# untitled.net
KiCad netlist of a schematic drawn in EAGLE
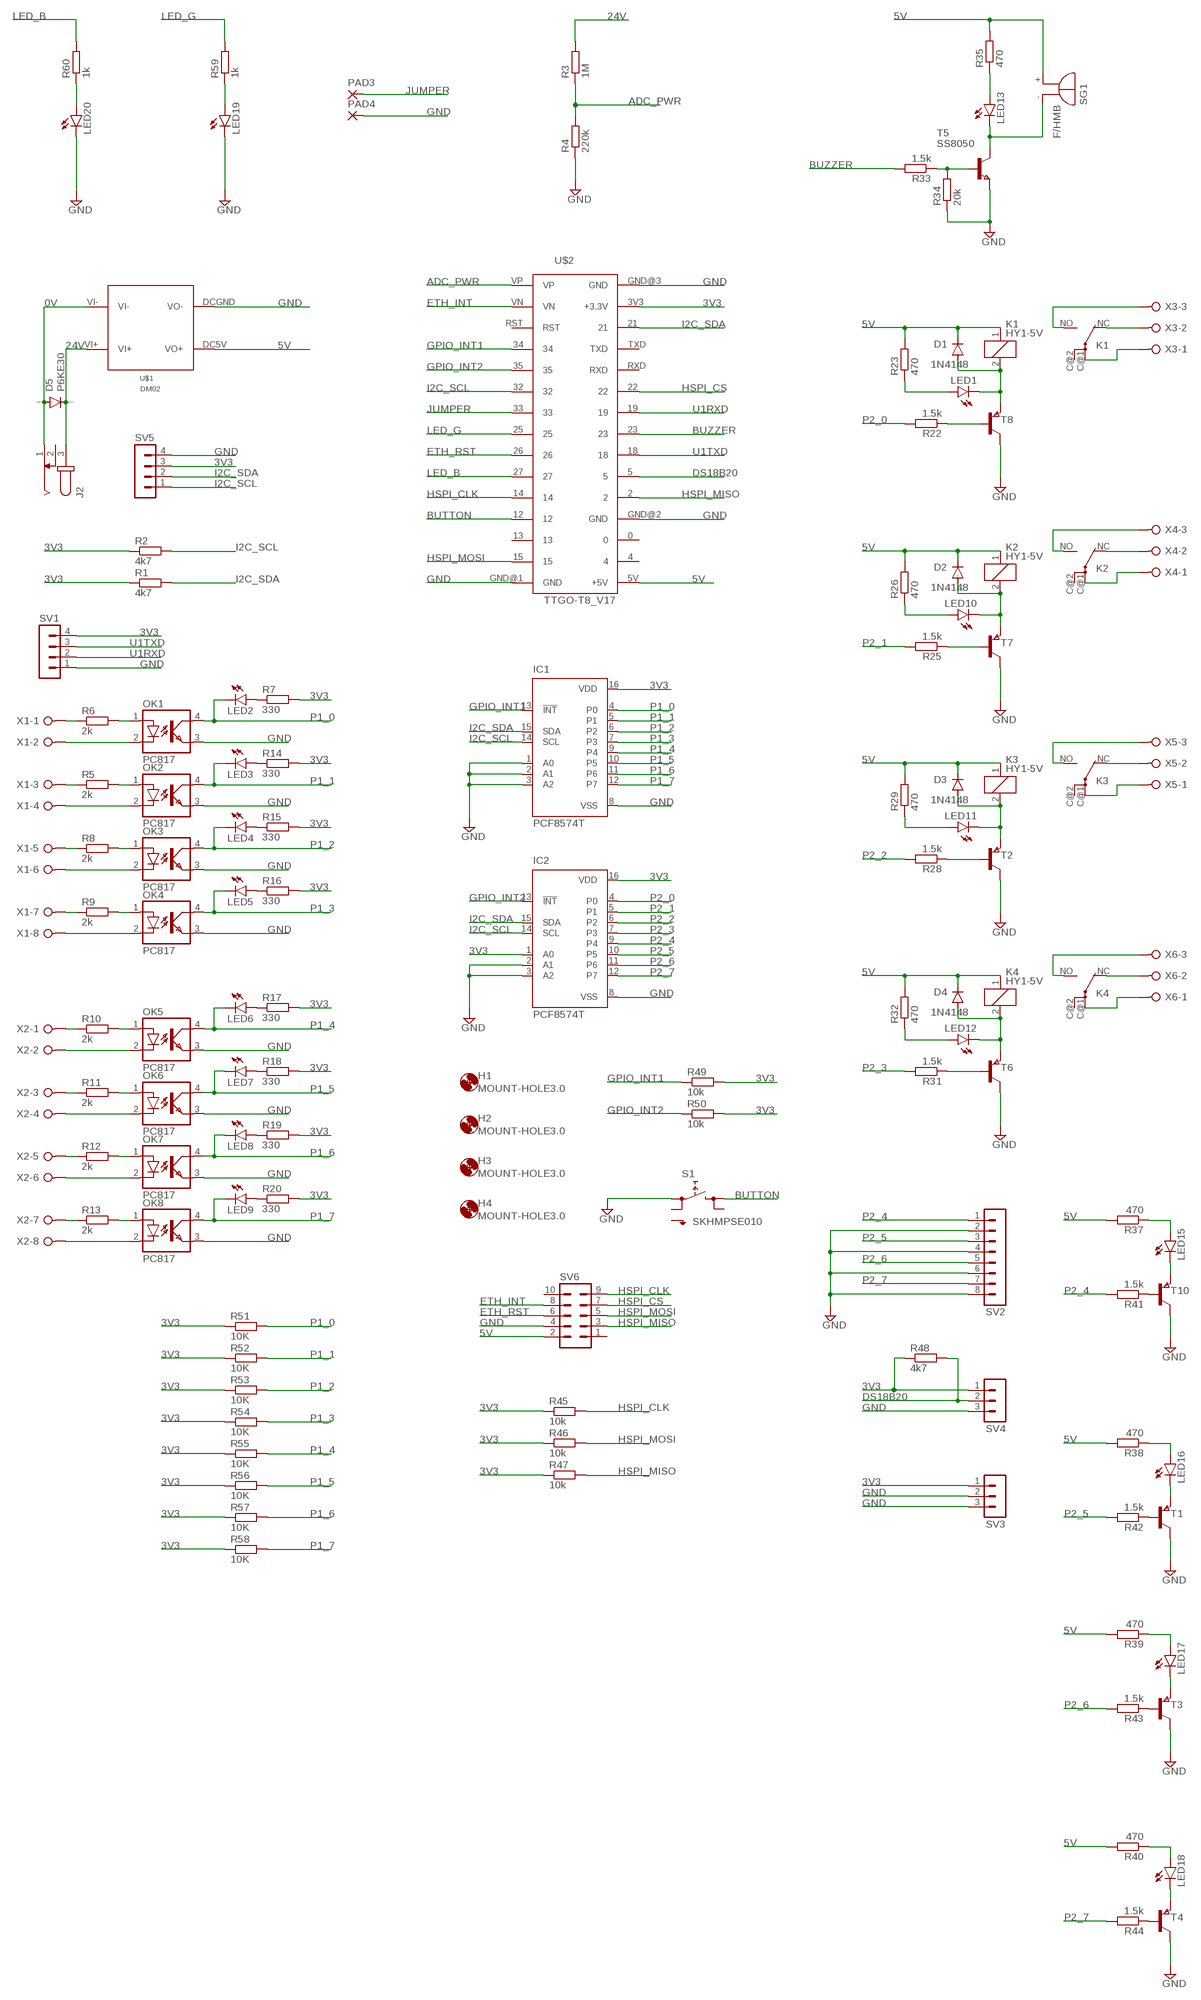
[diagram p0: schematic, sheet 1]

(export (version "E")
  (design (tool "Eeschema 10.0.6"))
  (components
    (comp (ref "D1")
      (value "1N4148")
      (footprint "eagle-import:SOD123")
      (libsource (lib "eagle-import") (part "DIODE-SOD123"))
    )
    (comp (ref "D2")
      (value "1N4148")
      (footprint "eagle-import:SOD123")
      (libsource (lib "eagle-import") (part "DIODE-SOD123"))
    )
    (comp (ref "D3")
      (value "1N4148")
      (footprint "eagle-import:SOD123")
      (libsource (lib "eagle-import") (part "DIODE-SOD123"))
    )
    (comp (ref "D4")
      (value "1N4148")
      (footprint "eagle-import:SOD123")
      (libsource (lib "eagle-import") (part "DIODE-SOD123"))
    )
    (comp (ref "D5")
      (value "P6KE30")
      (footprint "eagle-import:D-10")
      (libsource (lib "eagle-import") (part "diode@1_DIODE-D-10"))
    )
    (comp (ref "H1")
      (value "MOUNT-HOLE3.0")
      (footprint "eagle-import:3,0")
      (libsource (lib "eagle-import") (part "MOUNT-HOLE3.0"))
    )
    (comp (ref "H2")
      (value "MOUNT-HOLE3.0")
      (footprint "eagle-import:3,0")
      (libsource (lib "eagle-import") (part "MOUNT-HOLE3.0"))
    )
    (comp (ref "H3")
      (value "MOUNT-HOLE3.0")
      (footprint "eagle-import:3,0")
      (libsource (lib "eagle-import") (part "MOUNT-HOLE3.0"))
    )
    (comp (ref "H4")
      (value "MOUNT-HOLE3.0")
      (footprint "eagle-import:3,0")
      (libsource (lib "eagle-import") (part "MOUNT-HOLE3.0"))
    )
    (comp (ref "IC1")
      (value "PCF8574T")
      (footprint "eagle-import:SO16W")
      (fields (field (name "MPN") "PCF8574T/3,512"))
      (libsource (lib "eagle-import") (part "PCF8574T"))
    )
    (comp (ref "IC2")
      (value "PCF8574T")
      (footprint "eagle-import:SO16W")
      (fields (field (name "MPN") "PCF8574T/3,512"))
      (libsource (lib "eagle-import") (part "PCF8574T"))
    )
    (comp (ref "J2")
      (value "JACK-PLUG0")
      (footprint "eagle-import:SPC4077")
      (libsource (lib "eagle-import") (part "JACK-PLUG0"))
    )
    (comp (ref "K1")
      (value "HY1-5V")
      (footprint "eagle-import:HY")
      (fields (field (name "MF") "AROMAT/ MATSUSHITA"))
      (libsource (lib "eagle-import") (part "HY1-5V"))
    )
    (comp (ref "K2")
      (value "HY1-5V")
      (footprint "eagle-import:HY")
      (fields (field (name "MF") "AROMAT/ MATSUSHITA"))
      (libsource (lib "eagle-import") (part "HY1-5V"))
    )
    (comp (ref "K3")
      (value "HY1-5V")
      (footprint "eagle-import:HY")
      (fields (field (name "MF") "AROMAT/ MATSUSHITA"))
      (libsource (lib "eagle-import") (part "HY1-5V"))
    )
    (comp (ref "K4")
      (value "HY1-5V")
      (footprint "eagle-import:HY")
      (fields (field (name "MF") "AROMAT/ MATSUSHITA"))
      (libsource (lib "eagle-import") (part "HY1-5V"))
    )
    (comp (ref "LED1")
      (value "LEDCHIPLED_0805")
      (footprint "eagle-import:CHIPLED_0805")
      (libsource (lib "eagle-import") (part "LEDCHIPLED_0805"))
    )
    (comp (ref "LED2")
      (value "LEDCHIPLED_0805")
      (footprint "eagle-import:CHIPLED_0805")
      (libsource (lib "eagle-import") (part "LEDCHIPLED_0805"))
    )
    (comp (ref "LED3")
      (value "LEDCHIPLED_0805")
      (footprint "eagle-import:CHIPLED_0805")
      (libsource (lib "eagle-import") (part "LEDCHIPLED_0805"))
    )
    (comp (ref "LED4")
      (value "LEDCHIPLED_0805")
      (footprint "eagle-import:CHIPLED_0805")
      (libsource (lib "eagle-import") (part "LEDCHIPLED_0805"))
    )
    (comp (ref "LED5")
      (value "LEDCHIPLED_0805")
      (footprint "eagle-import:CHIPLED_0805")
      (libsource (lib "eagle-import") (part "LEDCHIPLED_0805"))
    )
    (comp (ref "LED6")
      (value "LEDCHIPLED_0805")
      (footprint "eagle-import:CHIPLED_0805")
      (libsource (lib "eagle-import") (part "LEDCHIPLED_0805"))
    )
    (comp (ref "LED7")
      (value "LEDCHIPLED_0805")
      (footprint "eagle-import:CHIPLED_0805")
      (libsource (lib "eagle-import") (part "LEDCHIPLED_0805"))
    )
    (comp (ref "LED8")
      (value "LEDCHIPLED_0805")
      (footprint "eagle-import:CHIPLED_0805")
      (libsource (lib "eagle-import") (part "LEDCHIPLED_0805"))
    )
    (comp (ref "LED9")
      (value "LEDCHIPLED_0805")
      (footprint "eagle-import:CHIPLED_0805")
      (libsource (lib "eagle-import") (part "LEDCHIPLED_0805"))
    )
    (comp (ref "LED10")
      (value "LEDCHIPLED_0805")
      (footprint "eagle-import:CHIPLED_0805")
      (libsource (lib "eagle-import") (part "LEDCHIPLED_0805"))
    )
    (comp (ref "LED11")
      (value "LEDCHIPLED_0805")
      (footprint "eagle-import:CHIPLED_0805")
      (libsource (lib "eagle-import") (part "LEDCHIPLED_0805"))
    )
    (comp (ref "LED12")
      (value "LEDCHIPLED_0805")
      (footprint "eagle-import:CHIPLED_0805")
      (libsource (lib "eagle-import") (part "LEDCHIPLED_0805"))
    )
    (comp (ref "LED13")
      (value "LEDCHIPLED_0805")
      (footprint "eagle-import:CHIPLED_0805")
      (libsource (lib "eagle-import") (part "LEDCHIPLED_0805"))
    )
    (comp (ref "LED15")
      (value "LEDCHIPLED_0805")
      (footprint "eagle-import:CHIPLED_0805")
      (libsource (lib "eagle-import") (part "LEDCHIPLED_0805"))
    )
    (comp (ref "LED16")
      (value "LEDCHIPLED_0805")
      (footprint "eagle-import:CHIPLED_0805")
      (libsource (lib "eagle-import") (part "LEDCHIPLED_0805"))
    )
    (comp (ref "LED17")
      (value "LEDCHIPLED_0805")
      (footprint "eagle-import:CHIPLED_0805")
      (libsource (lib "eagle-import") (part "LEDCHIPLED_0805"))
    )
    (comp (ref "LED18")
      (value "LEDCHIPLED_0805")
      (footprint "eagle-import:CHIPLED_0805")
      (libsource (lib "eagle-import") (part "LEDCHIPLED_0805"))
    )
    (comp (ref "LED19")
      (value "LEDCHIPLED_0805")
      (footprint "eagle-import:CHIPLED_0805")
      (libsource (lib "eagle-import") (part "LEDCHIPLED_0805"))
    )
    (comp (ref "LED20")
      (value "LEDCHIPLED_0805")
      (footprint "eagle-import:CHIPLED_0805")
      (libsource (lib "eagle-import") (part "LEDCHIPLED_0805"))
    )
    (comp (ref "OK1")
      (value "PC817")
      (footprint "eagle-import:DIL04")
      (fields (field (name "MPN") "PC817X4J000F"))
      (libsource (lib "eagle-import") (part "PC817"))
    )
    (comp (ref "OK2")
      (value "PC817")
      (footprint "eagle-import:DIL04")
      (fields (field (name "MPN") "PC817X4J000F"))
      (libsource (lib "eagle-import") (part "PC817"))
    )
    (comp (ref "OK3")
      (value "PC817")
      (footprint "eagle-import:DIL04")
      (fields (field (name "MPN") "PC817X4J000F"))
      (libsource (lib "eagle-import") (part "PC817"))
    )
    (comp (ref "OK4")
      (value "PC817")
      (footprint "eagle-import:DIL04")
      (fields (field (name "MPN") "PC817X4J000F"))
      (libsource (lib "eagle-import") (part "PC817"))
    )
    (comp (ref "OK5")
      (value "PC817")
      (footprint "eagle-import:DIL04")
      (fields (field (name "MPN") "PC817X4J000F"))
      (libsource (lib "eagle-import") (part "PC817"))
    )
    (comp (ref "OK6")
      (value "PC817")
      (footprint "eagle-import:DIL04")
      (fields (field (name "MPN") "PC817X4J000F"))
      (libsource (lib "eagle-import") (part "PC817"))
    )
    (comp (ref "OK7")
      (value "PC817")
      (footprint "eagle-import:DIL04")
      (fields (field (name "MPN") "PC817X4J000F"))
      (libsource (lib "eagle-import") (part "PC817"))
    )
    (comp (ref "OK8")
      (value "PC817")
      (footprint "eagle-import:DIL04")
      (fields (field (name "MPN") "PC817X4J000F"))
      (libsource (lib "eagle-import") (part "PC817"))
    )
    (comp (ref "PAD3")
      (value "2,15/1,0")
      (footprint "eagle-import:2,15_1,0")
      (libsource (lib "eagle-import") (part "2,15/1,0"))
    )
    (comp (ref "PAD4")
      (value "2,15/1,0")
      (footprint "eagle-import:2,15_1,0")
      (libsource (lib "eagle-import") (part "2,15/1,0"))
    )
    (comp (ref "R1")
      (value "4k7")
      (footprint "eagle-import:R0603")
      (libsource (lib "eagle-import") (part "R-EU_R0603"))
    )
    (comp (ref "R2")
      (value "4k7")
      (footprint "eagle-import:R0603")
      (libsource (lib "eagle-import") (part "R-EU_R0603"))
    )
    (comp (ref "R3")
      (value "1M")
      (footprint "eagle-import:R0603")
      (libsource (lib "eagle-import") (part "R-EU_R0603"))
    )
    (comp (ref "R4")
      (value "220k")
      (footprint "eagle-import:R0603")
      (libsource (lib "eagle-import") (part "R-EU_R0603"))
    )
    (comp (ref "R5")
      (value "2k")
      (footprint "eagle-import:R0603")
      (libsource (lib "eagle-import") (part "R-EU_R0603"))
    )
    (comp (ref "R6")
      (value "2k")
      (footprint "eagle-import:R0603")
      (libsource (lib "eagle-import") (part "R-EU_R0603"))
    )
    (comp (ref "R7")
      (value "330")
      (footprint "eagle-import:R0603")
      (libsource (lib "eagle-import") (part "R-EU_R0603"))
    )
    (comp (ref "R8")
      (value "2k")
      (footprint "eagle-import:R0603")
      (libsource (lib "eagle-import") (part "R-EU_R0603"))
    )
    (comp (ref "R9")
      (value "2k")
      (footprint "eagle-import:R0603")
      (libsource (lib "eagle-import") (part "R-EU_R0603"))
    )
    (comp (ref "R10")
      (value "2k")
      (footprint "eagle-import:R0603")
      (libsource (lib "eagle-import") (part "R-EU_R0603"))
    )
    (comp (ref "R11")
      (value "2k")
      (footprint "eagle-import:R0603")
      (libsource (lib "eagle-import") (part "R-EU_R0603"))
    )
    (comp (ref "R12")
      (value "2k")
      (footprint "eagle-import:R0603")
      (libsource (lib "eagle-import") (part "R-EU_R0603"))
    )
    (comp (ref "R13")
      (value "2k")
      (footprint "eagle-import:R0603")
      (libsource (lib "eagle-import") (part "R-EU_R0603"))
    )
    (comp (ref "R14")
      (value "330")
      (footprint "eagle-import:R0603")
      (libsource (lib "eagle-import") (part "R-EU_R0603"))
    )
    (comp (ref "R15")
      (value "330")
      (footprint "eagle-import:R0603")
      (libsource (lib "eagle-import") (part "R-EU_R0603"))
    )
    (comp (ref "R16")
      (value "330")
      (footprint "eagle-import:R0603")
      (libsource (lib "eagle-import") (part "R-EU_R0603"))
    )
    (comp (ref "R17")
      (value "330")
      (footprint "eagle-import:R0603")
      (libsource (lib "eagle-import") (part "R-EU_R0603"))
    )
    (comp (ref "R18")
      (value "330")
      (footprint "eagle-import:R0603")
      (libsource (lib "eagle-import") (part "R-EU_R0603"))
    )
    (comp (ref "R19")
      (value "330")
      (footprint "eagle-import:R0603")
      (libsource (lib "eagle-import") (part "R-EU_R0603"))
    )
    (comp (ref "R20")
      (value "330")
      (footprint "eagle-import:R0603")
      (libsource (lib "eagle-import") (part "R-EU_R0603"))
    )
    (comp (ref "R22")
      (value "1.5k")
      (footprint "eagle-import:R0603")
      (libsource (lib "eagle-import") (part "R-EU_R0603"))
    )
    (comp (ref "R23")
      (value "470")
      (footprint "eagle-import:R0603")
      (libsource (lib "eagle-import") (part "R-EU_R0603"))
    )
    (comp (ref "R25")
      (value "1.5k")
      (footprint "eagle-import:R0603")
      (libsource (lib "eagle-import") (part "R-EU_R0603"))
    )
    (comp (ref "R26")
      (value "470")
      (footprint "eagle-import:R0603")
      (libsource (lib "eagle-import") (part "R-EU_R0603"))
    )
    (comp (ref "R28")
      (value "1.5k")
      (footprint "eagle-import:R0603")
      (libsource (lib "eagle-import") (part "R-EU_R0603"))
    )
    (comp (ref "R29")
      (value "470")
      (footprint "eagle-import:R0603")
      (libsource (lib "eagle-import") (part "R-EU_R0603"))
    )
    (comp (ref "R31")
      (value "1.5k")
      (footprint "eagle-import:R0603")
      (libsource (lib "eagle-import") (part "R-EU_R0603"))
    )
    (comp (ref "R32")
      (value "470")
      (footprint "eagle-import:R0603")
      (libsource (lib "eagle-import") (part "R-EU_R0603"))
    )
    (comp (ref "R33")
      (value "1.5k")
      (footprint "eagle-import:R0603")
      (libsource (lib "eagle-import") (part "R-EU_R0603"))
    )
    (comp (ref "R34")
      (value "20k")
      (footprint "eagle-import:R0603")
      (libsource (lib "eagle-import") (part "R-EU_R0603"))
    )
    (comp (ref "R35")
      (value "470")
      (footprint "eagle-import:R0603")
      (libsource (lib "eagle-import") (part "R-EU_R0603"))
    )
    (comp (ref "R37")
      (value "470")
      (footprint "eagle-import:R0603")
      (libsource (lib "eagle-import") (part "R-EU_R0603"))
    )
    (comp (ref "R38")
      (value "470")
      (footprint "eagle-import:R0603")
      (libsource (lib "eagle-import") (part "R-EU_R0603"))
    )
    (comp (ref "R39")
      (value "470")
      (footprint "eagle-import:R0603")
      (libsource (lib "eagle-import") (part "R-EU_R0603"))
    )
    (comp (ref "R40")
      (value "470")
      (footprint "eagle-import:R0603")
      (libsource (lib "eagle-import") (part "R-EU_R0603"))
    )
    (comp (ref "R41")
      (value "1.5k")
      (footprint "eagle-import:R0603")
      (libsource (lib "eagle-import") (part "R-EU_R0603"))
    )
    (comp (ref "R42")
      (value "1.5k")
      (footprint "eagle-import:R0603")
      (libsource (lib "eagle-import") (part "R-EU_R0603"))
    )
    (comp (ref "R43")
      (value "1.5k")
      (footprint "eagle-import:R0603")
      (libsource (lib "eagle-import") (part "R-EU_R0603"))
    )
    (comp (ref "R44")
      (value "1.5k")
      (footprint "eagle-import:R0603")
      (libsource (lib "eagle-import") (part "R-EU_R0603"))
    )
    (comp (ref "R45")
      (value "10k")
      (footprint "eagle-import:R0603")
      (libsource (lib "eagle-import") (part "R-EU_R0603"))
    )
    (comp (ref "R46")
      (value "10k")
      (footprint "eagle-import:R0603")
      (libsource (lib "eagle-import") (part "R-EU_R0603"))
    )
    (comp (ref "R47")
      (value "10k")
      (footprint "eagle-import:R0603")
      (libsource (lib "eagle-import") (part "R-EU_R0603"))
    )
    (comp (ref "R48")
      (value "4k7")
      (footprint "eagle-import:R0603")
      (libsource (lib "eagle-import") (part "R-EU_R0603"))
    )
    (comp (ref "R49")
      (value "10k")
      (footprint "eagle-import:R0603")
      (libsource (lib "eagle-import") (part "R-EU_R0603"))
    )
    (comp (ref "R50")
      (value "10k")
      (footprint "eagle-import:R0603")
      (libsource (lib "eagle-import") (part "R-EU_R0603"))
    )
    (comp (ref "R51")
      (value "10K")
      (footprint "eagle-import:R0603")
      (libsource (lib "eagle-import") (part "R-EU_R0603"))
    )
    (comp (ref "R52")
      (value "10K")
      (footprint "eagle-import:R0603")
      (libsource (lib "eagle-import") (part "R-EU_R0603"))
    )
    (comp (ref "R53")
      (value "10K")
      (footprint "eagle-import:R0603")
      (libsource (lib "eagle-import") (part "R-EU_R0603"))
    )
    (comp (ref "R54")
      (value "10K")
      (footprint "eagle-import:R0603")
      (libsource (lib "eagle-import") (part "R-EU_R0603"))
    )
    (comp (ref "R55")
      (value "10K")
      (footprint "eagle-import:R0603")
      (libsource (lib "eagle-import") (part "R-EU_R0603"))
    )
    (comp (ref "R56")
      (value "10K")
      (footprint "eagle-import:R0603")
      (libsource (lib "eagle-import") (part "R-EU_R0603"))
    )
    (comp (ref "R57")
      (value "10K")
      (footprint "eagle-import:R0603")
      (libsource (lib "eagle-import") (part "R-EU_R0603"))
    )
    (comp (ref "R58")
      (value "10K")
      (footprint "eagle-import:R0603")
      (libsource (lib "eagle-import") (part "R-EU_R0603"))
    )
    (comp (ref "R59")
      (value "1k")
      (footprint "eagle-import:R0603")
      (libsource (lib "eagle-import") (part "R-EU_R0603"))
    )
    (comp (ref "R60")
      (value "1k")
      (footprint "eagle-import:R0603")
      (libsource (lib "eagle-import") (part "R-EU_R0603"))
    )
    (comp (ref "S1")
      (value "SKHMPSE010")
      (footprint "eagle-import:SKHMPXE010")
      (libsource (lib "eagle-import") (part "SKHMPE010S"))
    )
    (comp (ref "SG1")
      (value "F/HMB")
      (footprint "eagle-import:F_HMB")
      (libsource (lib "eagle-import") (part "F/HMB"))
    )
    (comp (ref "SV1")
      (value "MA04-1")
      (footprint "eagle-import:MA04-1")
      (libsource (lib "eagle-import") (part "MA04-1"))
    )
    (comp (ref "SV2")
      (value "MA08-1")
      (footprint "eagle-import:MA08-1")
      (libsource (lib "eagle-import") (part "MA08-1"))
    )
    (comp (ref "SV3")
      (value "MA03-1")
      (footprint "eagle-import:MA03-1")
      (libsource (lib "eagle-import") (part "MA03-1"))
    )
    (comp (ref "SV4")
      (value "MA03-1")
      (footprint "eagle-import:MA03-1")
      (libsource (lib "eagle-import") (part "MA03-1"))
    )
    (comp (ref "SV5")
      (value "MA04-1")
      (footprint "eagle-import:MA04-1")
      (libsource (lib "eagle-import") (part "MA04-1"))
    )
    (comp (ref "SV6")
      (value "MA05-2")
      (footprint "eagle-import:MA05-2")
      (libsource (lib "eagle-import") (part "MA05-2"))
    )
    (comp (ref "T1")
      (value "PNPSOT23")
      (footprint "eagle-import:SOT-23")
      (fields (field (name "MPN") "DSS20200L-7"))
      (libsource (lib "eagle-import") (part "PNPSOT23"))
    )
    (comp (ref "T2")
      (value "PNPSOT23")
      (footprint "eagle-import:SOT-23")
      (fields (field (name "MPN") "DSS20200L-7"))
      (libsource (lib "eagle-import") (part "PNPSOT23"))
    )
    (comp (ref "T3")
      (value "PNPSOT23")
      (footprint "eagle-import:SOT-23")
      (fields (field (name "MPN") "DSS20200L-7"))
      (libsource (lib "eagle-import") (part "PNPSOT23"))
    )
    (comp (ref "T4")
      (value "PNPSOT23")
      (footprint "eagle-import:SOT-23")
      (fields (field (name "MPN") "DSS20200L-7"))
      (libsource (lib "eagle-import") (part "PNPSOT23"))
    )
    (comp (ref "T5")
      (value "SS8050")
      (footprint "eagle-import:SOT-23")
      (fields (field (name "MPN") "DSS20201L-7"))
      (libsource (lib "eagle-import") (part "NPNSOT23"))
    )
    (comp (ref "T6")
      (value "PNPSOT23")
      (footprint "eagle-import:SOT-23")
      (fields (field (name "MPN") "DSS20200L-7"))
      (libsource (lib "eagle-import") (part "PNPSOT23"))
    )
    (comp (ref "T7")
      (value "PNPSOT23")
      (footprint "eagle-import:SOT-23")
      (fields (field (name "MPN") "DSS20200L-7"))
      (libsource (lib "eagle-import") (part "PNPSOT23"))
    )
    (comp (ref "T8")
      (value "PNPSOT23")
      (footprint "eagle-import:SOT-23")
      (fields (field (name "MPN") "DSS20200L-7"))
      (libsource (lib "eagle-import") (part "PNPSOT23"))
    )
    (comp (ref "T10")
      (value "PNPSOT23")
      (footprint "eagle-import:SOT-23")
      (fields (field (name "MPN") "DSS20200L-7"))
      (libsource (lib "eagle-import") (part "PNPSOT23"))
    )
    (comp (ref "U$1")
      (value "DM02")
      (footprint "eagle-import:DM02")
      (libsource (lib "eagle-import") (part "DM02"))
    )
    (comp (ref "U$2")
      (value "TTGO-T8_V17")
      (footprint "eagle-import:TTGO-T8_V17")
      (libsource (lib "eagle-import") (part "TTGO-T8_V17"))
    )
    (comp (ref "X1")
      (value "W237-08P")
      (footprint "eagle-import:W237-8P")
      (libsource (lib "eagle-import") (part "W237-08P"))
    )
    (comp (ref "X2")
      (value "W237-08P")
      (footprint "eagle-import:W237-8P")
      (libsource (lib "eagle-import") (part "W237-08P"))
    )
    (comp (ref "X3")
      (value "W237-03P")
      (footprint "eagle-import:W237-133")
      (libsource (lib "eagle-import") (part "W237-03P"))
    )
    (comp (ref "X4")
      (value "W237-03P")
      (footprint "eagle-import:W237-133")
      (libsource (lib "eagle-import") (part "W237-03P"))
    )
    (comp (ref "X5")
      (value "W237-03P")
      (footprint "eagle-import:W237-133")
      (libsource (lib "eagle-import") (part "W237-03P"))
    )
    (comp (ref "X6")
      (value "W237-03P")
      (footprint "eagle-import:W237-133")
      (libsource (lib "eagle-import") (part "W237-03P"))
    )
  )
  (nets
    (net (code "1") (name "/0V") (class "Default")
      (node (ref "D5") (pin "A") (pinfunction "A_A") (pintype "passive"))
      (node (ref "J2") (pin "1") (pinfunction "1_1") (pintype "passive"))
      (node (ref "U$1") (pin "VI-") (pinfunction "VI-_VI-") (pintype "bidirectional"))
    )
    (net (code "2") (name "/3V3") (class "Default")
      (node (ref "IC1") (pin "16") (pinfunction "VDD_16") (pintype "power_in"))
      (node (ref "IC2") (pin "1") (pinfunction "A0_1") (pintype "input"))
      (node (ref "IC2") (pin "16") (pinfunction "VDD_16") (pintype "power_in"))
      (node (ref "R1") (pin "1") (pinfunction "1_1") (pintype "passive"))
      (node (ref "R14") (pin "2") (pinfunction "2_2") (pintype "passive"))
      (node (ref "R15") (pin "2") (pinfunction "2_2") (pintype "passive"))
      (node (ref "R16") (pin "2") (pinfunction "2_2") (pintype "passive"))
      (node (ref "R17") (pin "2") (pinfunction "2_2") (pintype "passive"))
      (node (ref "R18") (pin "2") (pinfunction "2_2") (pintype "passive"))
      (node (ref "R19") (pin "2") (pinfunction "2_2") (pintype "passive"))
      (node (ref "R2") (pin "1") (pinfunction "1_1") (pintype "passive"))
      (node (ref "R20") (pin "2") (pinfunction "2_2") (pintype "passive"))
      (node (ref "R45") (pin "1") (pinfunction "1_1") (pintype "passive"))
      (node (ref "R46") (pin "1") (pinfunction "1_1") (pintype "passive"))
      (node (ref "R47") (pin "1") (pinfunction "1_1") (pintype "passive"))
      (node (ref "R48") (pin "1") (pinfunction "1_1") (pintype "passive"))
      (node (ref "R49") (pin "2") (pinfunction "2_2") (pintype "passive"))
      (node (ref "R50") (pin "2") (pinfunction "2_2") (pintype "passive"))
      (node (ref "R51") (pin "1") (pinfunction "1_1") (pintype "passive"))
      (node (ref "R52") (pin "1") (pinfunction "1_1") (pintype "passive"))
      (node (ref "R53") (pin "1") (pinfunction "1_1") (pintype "passive"))
      (node (ref "R54") (pin "1") (pinfunction "1_1") (pintype "passive"))
      (node (ref "R55") (pin "1") (pinfunction "1_1") (pintype "passive"))
      (node (ref "R56") (pin "1") (pinfunction "1_1") (pintype "passive"))
      (node (ref "R57") (pin "1") (pinfunction "1_1") (pintype "passive"))
      (node (ref "R58") (pin "1") (pinfunction "1_1") (pintype "passive"))
      (node (ref "R7") (pin "2") (pinfunction "2_2") (pintype "passive"))
      (node (ref "SV1") (pin "4") (pinfunction "4_4") (pintype "passive"))
      (node (ref "SV3") (pin "1") (pinfunction "1_1") (pintype "passive"))
      (node (ref "SV4") (pin "1") (pinfunction "1_1") (pintype "passive"))
      (node (ref "SV5") (pin "3") (pinfunction "3_3") (pintype "passive"))
      (node (ref "U$2") (pin "3V3") (pinfunction "+3.3V_3V3") (pintype "bidirectional"))
    )
    (net (code "3") (name "/5V") (class "Default")
      (node (ref "D1") (pin "C") (pinfunction "C_C") (pintype "passive"))
      (node (ref "D2") (pin "C") (pinfunction "C_C") (pintype "passive"))
      (node (ref "D3") (pin "C") (pinfunction "C_C") (pintype "passive"))
      (node (ref "D4") (pin "C") (pinfunction "C_C") (pintype "passive"))
      (node (ref "K1") (pin "1") (pinfunction "1_1") (pintype "passive"))
      (node (ref "K2") (pin "1") (pinfunction "1_1") (pintype "passive"))
      (node (ref "K3") (pin "1") (pinfunction "1_1") (pintype "passive"))
      (node (ref "K4") (pin "1") (pinfunction "1_1") (pintype "passive"))
      (node (ref "R23") (pin "2") (pinfunction "2_2") (pintype "passive"))
      (node (ref "R26") (pin "2") (pinfunction "2_2") (pintype "passive"))
      (node (ref "R29") (pin "2") (pinfunction "2_2") (pintype "passive"))
      (node (ref "R32") (pin "2") (pinfunction "2_2") (pintype "passive"))
      (node (ref "R35") (pin "2") (pinfunction "2_2") (pintype "passive"))
      (node (ref "R37") (pin "2") (pinfunction "2_2") (pintype "passive"))
      (node (ref "R38") (pin "2") (pinfunction "2_2") (pintype "passive"))
      (node (ref "R39") (pin "2") (pinfunction "2_2") (pintype "passive"))
      (node (ref "R40") (pin "2") (pinfunction "2_2") (pintype "passive"))
      (node (ref "SG1") (pin "+") (pinfunction "+_+") (pintype "passive"))
      (node (ref "SV6") (pin "2") (pinfunction "2_2") (pintype "passive"))
      (node (ref "U$1") (pin "DC5V") (pinfunction "VO+_DC5V") (pintype "bidirectional"))
      (node (ref "U$2") (pin "5V") (pinfunction "+5V_5V") (pintype "bidirectional"))
    )
    (net (code "4") (name "/24V") (class "Default")
      (node (ref "D5") (pin "C") (pinfunction "C_C") (pintype "passive"))
      (node (ref "J2") (pin "3") (pinfunction "3_3") (pintype "passive"))
      (node (ref "R3") (pin "2") (pinfunction "2_2") (pintype "passive"))
      (node (ref "U$1") (pin "VI+") (pinfunction "VI+_VI+") (pintype "bidirectional"))
    )
    (net (code "5") (name "/ADC_PWR") (class "Default")
      (node (ref "R3") (pin "1") (pinfunction "1_1") (pintype "passive"))
      (node (ref "R4") (pin "2") (pinfunction "2_2") (pintype "passive"))
      (node (ref "U$2") (pin "VP") (pinfunction "VP_VP") (pintype "bidirectional"))
    )
    (net (code "6") (name "/BUTTON") (class "Default")
      (node (ref "S1") (pin "3") (pinfunction "2.1_3") (pintype "passive"))
      (node (ref "U$2") (pin "12") (pinfunction "12_12") (pintype "bidirectional"))
    )
    (net (code "7") (name "/BUZZER") (class "Default")
      (node (ref "R33") (pin "2") (pinfunction "2_2") (pintype "passive"))
      (node (ref "U$2") (pin "23") (pinfunction "23_23") (pintype "bidirectional"))
    )
    (net (code "8") (name "/DS18B20") (class "Default")
      (node (ref "R48") (pin "2") (pinfunction "2_2") (pintype "passive"))
      (node (ref "SV4") (pin "2") (pinfunction "2_2") (pintype "passive"))
      (node (ref "U$2") (pin "5") (pinfunction "5_5") (pintype "bidirectional"))
    )
    (net (code "9") (name "/ETH_INT") (class "Default")
      (node (ref "SV6") (pin "8") (pinfunction "8_8") (pintype "passive"))
      (node (ref "U$2") (pin "VN") (pinfunction "VN_VN") (pintype "bidirectional"))
    )
    (net (code "10") (name "/ETH_RST") (class "Default")
      (node (ref "SV6") (pin "6") (pinfunction "6_6") (pintype "passive"))
      (node (ref "U$2") (pin "26") (pinfunction "26_26") (pintype "bidirectional"))
    )
    (net (code "11") (name "/GPIO_INT1") (class "Default")
      (node (ref "IC1") (pin "13") (pinfunction "~{INT}_13") (pintype "output"))
      (node (ref "R49") (pin "1") (pinfunction "1_1") (pintype "passive"))
      (node (ref "U$2") (pin "34") (pinfunction "34_34") (pintype "bidirectional"))
    )
    (net (code "12") (name "/GPIO_INT2") (class "Default")
      (node (ref "IC2") (pin "13") (pinfunction "~{INT}_13") (pintype "output"))
      (node (ref "R50") (pin "1") (pinfunction "1_1") (pintype "passive"))
      (node (ref "U$2") (pin "35") (pinfunction "35_35") (pintype "bidirectional"))
    )
    (net (code "13") (name "/HSPI_CLK") (class "Default")
      (node (ref "R45") (pin "2") (pinfunction "2_2") (pintype "passive"))
      (node (ref "SV6") (pin "9") (pinfunction "9_9") (pintype "passive"))
      (node (ref "U$2") (pin "14") (pinfunction "14_14") (pintype "bidirectional"))
    )
    (net (code "14") (name "/HSPI_CS") (class "Default")
      (node (ref "SV6") (pin "7") (pinfunction "7_7") (pintype "passive"))
      (node (ref "U$2") (pin "22") (pinfunction "22_22") (pintype "bidirectional"))
    )
    (net (code "15") (name "/HSPI_MISO") (class "Default")
      (node (ref "R47") (pin "2") (pinfunction "2_2") (pintype "passive"))
      (node (ref "SV6") (pin "3") (pinfunction "3_3") (pintype "passive"))
      (node (ref "U$2") (pin "2") (pinfunction "2_2") (pintype "bidirectional"))
    )
    (net (code "16") (name "/HSPI_MOSI") (class "Default")
      (node (ref "R46") (pin "2") (pinfunction "2_2") (pintype "passive"))
      (node (ref "SV6") (pin "5") (pinfunction "5_5") (pintype "passive"))
      (node (ref "U$2") (pin "15") (pinfunction "15_15") (pintype "bidirectional"))
    )
    (net (code "17") (name "/I2C_SCL") (class "Default")
      (node (ref "IC1") (pin "14") (pinfunction "SCL_14") (pintype "input"))
      (node (ref "IC2") (pin "14") (pinfunction "SCL_14") (pintype "input"))
      (node (ref "R2") (pin "2") (pinfunction "2_2") (pintype "passive"))
      (node (ref "SV5") (pin "1") (pinfunction "1_1") (pintype "passive"))
      (node (ref "U$2") (pin "32") (pinfunction "32_32") (pintype "bidirectional"))
    )
    (net (code "18") (name "/I2C_SDA") (class "Default")
      (node (ref "IC1") (pin "15") (pinfunction "SDA_15") (pintype "bidirectional"))
      (node (ref "IC2") (pin "15") (pinfunction "SDA_15") (pintype "bidirectional"))
      (node (ref "R1") (pin "2") (pinfunction "2_2") (pintype "passive"))
      (node (ref "SV5") (pin "2") (pinfunction "2_2") (pintype "passive"))
      (node (ref "U$2") (pin "21") (pinfunction "21_21") (pintype "bidirectional"))
    )
    (net (code "19") (name "/JUMPER") (class "Default")
      (node (ref "PAD3") (pin "1") (pinfunction "P_1") (pintype "passive"))
      (node (ref "U$2") (pin "33") (pinfunction "33_33") (pintype "bidirectional"))
    )
    (net (code "20") (name "/LED_B") (class "Default")
      (node (ref "R60") (pin "2") (pinfunction "2_2") (pintype "passive"))
      (node (ref "U$2") (pin "27") (pinfunction "27_27") (pintype "bidirectional"))
    )
    (net (code "21") (name "/LED_G") (class "Default")
      (node (ref "R59") (pin "2") (pinfunction "2_2") (pintype "passive"))
      (node (ref "U$2") (pin "25") (pinfunction "25_25") (pintype "bidirectional"))
    )
    (net (code "22") (name "/P1_0") (class "Default")
      (node (ref "IC1") (pin "4") (pinfunction "P0_4") (pintype "bidirectional"))
      (node (ref "LED2") (pin "C") (pinfunction "C_C") (pintype "passive"))
      (node (ref "OK1") (pin "4") (pinfunction "COL_4") (pintype "passive"))
      (node (ref "R51") (pin "2") (pinfunction "2_2") (pintype "passive"))
    )
    (net (code "23") (name "/P1_1") (class "Default")
      (node (ref "IC1") (pin "5") (pinfunction "P1_5") (pintype "bidirectional"))
      (node (ref "LED3") (pin "C") (pinfunction "C_C") (pintype "passive"))
      (node (ref "OK2") (pin "4") (pinfunction "COL_4") (pintype "passive"))
      (node (ref "R52") (pin "2") (pinfunction "2_2") (pintype "passive"))
    )
    (net (code "24") (name "/P1_2") (class "Default")
      (node (ref "IC1") (pin "6") (pinfunction "P2_6") (pintype "bidirectional"))
      (node (ref "LED4") (pin "C") (pinfunction "C_C") (pintype "passive"))
      (node (ref "OK3") (pin "4") (pinfunction "COL_4") (pintype "passive"))
      (node (ref "R53") (pin "2") (pinfunction "2_2") (pintype "passive"))
    )
    (net (code "25") (name "/P1_3") (class "Default")
      (node (ref "IC1") (pin "7") (pinfunction "P3_7") (pintype "bidirectional"))
      (node (ref "LED5") (pin "C") (pinfunction "C_C") (pintype "passive"))
      (node (ref "OK4") (pin "4") (pinfunction "COL_4") (pintype "passive"))
      (node (ref "R54") (pin "2") (pinfunction "2_2") (pintype "passive"))
    )
    (net (code "26") (name "/P1_4") (class "Default")
      (node (ref "IC1") (pin "9") (pinfunction "P4_9") (pintype "bidirectional"))
      (node (ref "LED6") (pin "C") (pinfunction "C_C") (pintype "passive"))
      (node (ref "OK5") (pin "4") (pinfunction "COL_4") (pintype "passive"))
      (node (ref "R55") (pin "2") (pinfunction "2_2") (pintype "passive"))
    )
    (net (code "27") (name "/P1_5") (class "Default")
      (node (ref "IC1") (pin "10") (pinfunction "P5_10") (pintype "bidirectional"))
      (node (ref "LED7") (pin "C") (pinfunction "C_C") (pintype "passive"))
      (node (ref "OK6") (pin "4") (pinfunction "COL_4") (pintype "passive"))
      (node (ref "R56") (pin "2") (pinfunction "2_2") (pintype "passive"))
    )
    (net (code "28") (name "/P1_6") (class "Default")
      (node (ref "IC1") (pin "11") (pinfunction "P6_11") (pintype "bidirectional"))
      (node (ref "LED8") (pin "C") (pinfunction "C_C") (pintype "passive"))
      (node (ref "OK7") (pin "4") (pinfunction "COL_4") (pintype "passive"))
      (node (ref "R57") (pin "2") (pinfunction "2_2") (pintype "passive"))
    )
    (net (code "29") (name "/P1_7") (class "Default")
      (node (ref "IC1") (pin "12") (pinfunction "P7_12") (pintype "bidirectional"))
      (node (ref "LED9") (pin "C") (pinfunction "C_C") (pintype "passive"))
      (node (ref "OK8") (pin "4") (pinfunction "COL_4") (pintype "passive"))
      (node (ref "R58") (pin "2") (pinfunction "2_2") (pintype "passive"))
    )
    (net (code "30") (name "/P2_0") (class "Default")
      (node (ref "IC2") (pin "4") (pinfunction "P0_4") (pintype "bidirectional"))
      (node (ref "R22") (pin "2") (pinfunction "2_2") (pintype "passive"))
    )
    (net (code "31") (name "/P2_1") (class "Default")
      (node (ref "IC2") (pin "5") (pinfunction "P1_5") (pintype "bidirectional"))
      (node (ref "R25") (pin "2") (pinfunction "2_2") (pintype "passive"))
    )
    (net (code "32") (name "/P2_2") (class "Default")
      (node (ref "IC2") (pin "6") (pinfunction "P2_6") (pintype "bidirectional"))
      (node (ref "R28") (pin "2") (pinfunction "2_2") (pintype "passive"))
    )
    (net (code "33") (name "/P2_3") (class "Default")
      (node (ref "IC2") (pin "7") (pinfunction "P3_7") (pintype "bidirectional"))
      (node (ref "R31") (pin "2") (pinfunction "2_2") (pintype "passive"))
    )
    (net (code "34") (name "/P2_4") (class "Default")
      (node (ref "IC2") (pin "9") (pinfunction "P4_9") (pintype "bidirectional"))
      (node (ref "R41") (pin "2") (pinfunction "2_2") (pintype "passive"))
      (node (ref "SV2") (pin "1") (pinfunction "1_1") (pintype "passive"))
    )
    (net (code "35") (name "/P2_5") (class "Default")
      (node (ref "IC2") (pin "10") (pinfunction "P5_10") (pintype "bidirectional"))
      (node (ref "R42") (pin "2") (pinfunction "2_2") (pintype "passive"))
      (node (ref "SV2") (pin "3") (pinfunction "3_3") (pintype "passive"))
    )
    (net (code "36") (name "/P2_6") (class "Default")
      (node (ref "IC2") (pin "11") (pinfunction "P6_11") (pintype "bidirectional"))
      (node (ref "R43") (pin "2") (pinfunction "2_2") (pintype "passive"))
      (node (ref "SV2") (pin "5") (pinfunction "5_5") (pintype "passive"))
    )
    (net (code "37") (name "/P2_7") (class "Default")
      (node (ref "IC2") (pin "12") (pinfunction "P7_12") (pintype "bidirectional"))
      (node (ref "R44") (pin "2") (pinfunction "2_2") (pintype "passive"))
      (node (ref "SV2") (pin "7") (pinfunction "7_7") (pintype "passive"))
    )
    (net (code "38") (name "/U1RXD") (class "Default")
      (node (ref "SV1") (pin "2") (pinfunction "2_2") (pintype "passive"))
      (node (ref "U$2") (pin "19") (pinfunction "19_19") (pintype "bidirectional"))
    )
    (net (code "39") (name "/U1TXD") (class "Default")
      (node (ref "SV1") (pin "3") (pinfunction "3_3") (pintype "passive"))
      (node (ref "U$2") (pin "18") (pinfunction "18_18") (pintype "bidirectional"))
    )
    (net (code "40") (name "GND") (class "Default")
      (node (ref "IC1") (pin "1") (pinfunction "A0_1") (pintype "input"))
      (node (ref "IC1") (pin "2") (pinfunction "A1_2") (pintype "input"))
      (node (ref "IC1") (pin "3") (pinfunction "A2_3") (pintype "input"))
      (node (ref "IC1") (pin "8") (pinfunction "VSS_8") (pintype "power_in"))
      (node (ref "IC2") (pin "2") (pinfunction "A1_2") (pintype "input"))
      (node (ref "IC2") (pin "3") (pinfunction "A2_3") (pintype "input"))
      (node (ref "IC2") (pin "8") (pinfunction "VSS_8") (pintype "power_in"))
      (node (ref "LED19") (pin "C") (pinfunction "C_C") (pintype "passive"))
      (node (ref "LED20") (pin "C") (pinfunction "C_C") (pintype "passive"))
      (node (ref "OK1") (pin "3") (pinfunction "EMIT_3") (pintype "passive"))
      (node (ref "OK2") (pin "3") (pinfunction "EMIT_3") (pintype "passive"))
      (node (ref "OK3") (pin "3") (pinfunction "EMIT_3") (pintype "passive"))
      (node (ref "OK4") (pin "3") (pinfunction "EMIT_3") (pintype "passive"))
      (node (ref "OK5") (pin "3") (pinfunction "EMIT_3") (pintype "passive"))
      (node (ref "OK6") (pin "3") (pinfunction "EMIT_3") (pintype "passive"))
      (node (ref "OK7") (pin "3") (pinfunction "EMIT_3") (pintype "passive"))
      (node (ref "OK8") (pin "3") (pinfunction "EMIT_3") (pintype "passive"))
      (node (ref "PAD4") (pin "1") (pinfunction "P_1") (pintype "passive"))
      (node (ref "R34") (pin "1") (pinfunction "1_1") (pintype "passive"))
      (node (ref "R4") (pin "1") (pinfunction "1_1") (pintype "passive"))
      (node (ref "S1") (pin "1") (pinfunction "1.1_1") (pintype "passive"))
      (node (ref "SV1") (pin "1") (pinfunction "1_1") (pintype "passive"))
      (node (ref "SV2") (pin "2") (pinfunction "2_2") (pintype "passive"))
      (node (ref "SV2") (pin "4") (pinfunction "4_4") (pintype "passive"))
      (node (ref "SV2") (pin "6") (pinfunction "6_6") (pintype "passive"))
      (node (ref "SV2") (pin "8") (pinfunction "8_8") (pintype "passive"))
      (node (ref "SV3") (pin "2") (pinfunction "2_2") (pintype "passive"))
      (node (ref "SV3") (pin "3") (pinfunction "3_3") (pintype "passive"))
      (node (ref "SV4") (pin "3") (pinfunction "3_3") (pintype "passive"))
      (node (ref "SV5") (pin "4") (pinfunction "4_4") (pintype "passive"))
      (node (ref "SV6") (pin "4") (pinfunction "4_4") (pintype "passive"))
      (node (ref "T1") (pin "1") (pinfunction "C_1") (pintype "passive"))
      (node (ref "T10") (pin "1") (pinfunction "C_1") (pintype "passive"))
      (node (ref "T2") (pin "1") (pinfunction "C_1") (pintype "passive"))
      (node (ref "T3") (pin "1") (pinfunction "C_1") (pintype "passive"))
      (node (ref "T4") (pin "1") (pinfunction "C_1") (pintype "passive"))
      (node (ref "T5") (pin "2") (pinfunction "E_2") (pintype "passive"))
      (node (ref "T6") (pin "1") (pinfunction "C_1") (pintype "passive"))
      (node (ref "T7") (pin "1") (pinfunction "C_1") (pintype "passive"))
      (node (ref "T8") (pin "1") (pinfunction "C_1") (pintype "passive"))
      (node (ref "U$1") (pin "DCGND") (pinfunction "VO-_DCGND") (pintype "bidirectional"))
      (node (ref "U$2") (pin "GND@1") (pinfunction "GND_GND@1") (pintype "bidirectional"))
      (node (ref "U$2") (pin "GND@2") (pinfunction "GND_GND@2") (pintype "bidirectional"))
      (node (ref "U$2") (pin "GND@3") (pinfunction "GND_GND@3") (pintype "bidirectional"))
    )
    (net (code "41") (name "Net-(K1B-O)") (class "Default")
      (node (ref "K1") (pin "NC") (pinfunction "O_NC") (pintype "passive"))
      (node (ref "X3") (pin "2") (pinfunction "KL_2") (pintype "passive"))
    )
    (net (code "42") (name "Net-(K1B-S)") (class "Default")
      (node (ref "K1") (pin "NO") (pinfunction "S_NO") (pintype "passive"))
      (node (ref "X3") (pin "3") (pinfunction "KL_3") (pintype "passive"))
    )
    (net (code "43") (name "Net-(K2B-O)") (class "Default")
      (node (ref "K2") (pin "NC") (pinfunction "O_NC") (pintype "passive"))
      (node (ref "X4") (pin "2") (pinfunction "KL_2") (pintype "passive"))
    )
    (net (code "44") (name "Net-(K2B-S)") (class "Default")
      (node (ref "K2") (pin "NO") (pinfunction "S_NO") (pintype "passive"))
      (node (ref "X4") (pin "3") (pinfunction "KL_3") (pintype "passive"))
    )
    (net (code "45") (name "Net-(K3B-O)") (class "Default")
      (node (ref "K3") (pin "NC") (pinfunction "O_NC") (pintype "passive"))
      (node (ref "X5") (pin "2") (pinfunction "KL_2") (pintype "passive"))
    )
    (net (code "46") (name "Net-(K3B-S)") (class "Default")
      (node (ref "K3") (pin "NO") (pinfunction "S_NO") (pintype "passive"))
      (node (ref "X5") (pin "3") (pinfunction "KL_3") (pintype "passive"))
    )
    (net (code "47") (name "Net-(K4B-O)") (class "Default")
      (node (ref "K4") (pin "NC") (pinfunction "O_NC") (pintype "passive"))
      (node (ref "X6") (pin "2") (pinfunction "KL_2") (pintype "passive"))
    )
    (net (code "48") (name "Net-(K4B-S)") (class "Default")
      (node (ref "K4") (pin "NO") (pinfunction "S_NO") (pintype "passive"))
      (node (ref "X6") (pin "3") (pinfunction "KL_3") (pintype "passive"))
    )
    (net (code "49") (name "Net-(LED1-PadA)") (class "Default")
      (node (ref "LED1") (pin "A") (pinfunction "A_A") (pintype "passive"))
      (node (ref "R23") (pin "1") (pinfunction "1_1") (pintype "passive"))
    )
    (net (code "50") (name "Net-(LED2-PadA)") (class "Default")
      (node (ref "LED2") (pin "A") (pinfunction "A_A") (pintype "passive"))
      (node (ref "R7") (pin "1") (pinfunction "1_1") (pintype "passive"))
    )
    (net (code "51") (name "Net-(LED3-PadA)") (class "Default")
      (node (ref "LED3") (pin "A") (pinfunction "A_A") (pintype "passive"))
      (node (ref "R14") (pin "1") (pinfunction "1_1") (pintype "passive"))
    )
    (net (code "52") (name "Net-(LED4-PadA)") (class "Default")
      (node (ref "LED4") (pin "A") (pinfunction "A_A") (pintype "passive"))
      (node (ref "R15") (pin "1") (pinfunction "1_1") (pintype "passive"))
    )
    (net (code "53") (name "Net-(LED5-PadA)") (class "Default")
      (node (ref "LED5") (pin "A") (pinfunction "A_A") (pintype "passive"))
      (node (ref "R16") (pin "1") (pinfunction "1_1") (pintype "passive"))
    )
    (net (code "54") (name "Net-(LED6-PadA)") (class "Default")
      (node (ref "LED6") (pin "A") (pinfunction "A_A") (pintype "passive"))
      (node (ref "R17") (pin "1") (pinfunction "1_1") (pintype "passive"))
    )
    (net (code "55") (name "Net-(LED7-PadA)") (class "Default")
      (node (ref "LED7") (pin "A") (pinfunction "A_A") (pintype "passive"))
      (node (ref "R18") (pin "1") (pinfunction "1_1") (pintype "passive"))
    )
    (net (code "56") (name "Net-(LED8-PadA)") (class "Default")
      (node (ref "LED8") (pin "A") (pinfunction "A_A") (pintype "passive"))
      (node (ref "R19") (pin "1") (pinfunction "1_1") (pintype "passive"))
    )
    (net (code "57") (name "Net-(LED9-PadA)") (class "Default")
      (node (ref "LED9") (pin "A") (pinfunction "A_A") (pintype "passive"))
      (node (ref "R20") (pin "1") (pinfunction "1_1") (pintype "passive"))
    )
    (net (code "58") (name "Net-(LED10-PadA)") (class "Default")
      (node (ref "LED10") (pin "A") (pinfunction "A_A") (pintype "passive"))
      (node (ref "R26") (pin "1") (pinfunction "1_1") (pintype "passive"))
    )
    (net (code "59") (name "Net-(LED11-PadA)") (class "Default")
      (node (ref "LED11") (pin "A") (pinfunction "A_A") (pintype "passive"))
      (node (ref "R29") (pin "1") (pinfunction "1_1") (pintype "passive"))
    )
    (net (code "60") (name "Net-(LED12-PadA)") (class "Default")
      (node (ref "LED12") (pin "A") (pinfunction "A_A") (pintype "passive"))
      (node (ref "R32") (pin "1") (pinfunction "1_1") (pintype "passive"))
    )
    (net (code "61") (name "Net-(LED13-PadA)") (class "Default")
      (node (ref "LED13") (pin "A") (pinfunction "A_A") (pintype "passive"))
      (node (ref "R35") (pin "1") (pinfunction "1_1") (pintype "passive"))
    )
    (net (code "62") (name "Net-(LED15-PadA)") (class "Default")
      (node (ref "LED15") (pin "A") (pinfunction "A_A") (pintype "passive"))
      (node (ref "R37") (pin "1") (pinfunction "1_1") (pintype "passive"))
    )
    (net (code "63") (name "Net-(LED16-PadA)") (class "Default")
      (node (ref "LED16") (pin "A") (pinfunction "A_A") (pintype "passive"))
      (node (ref "R38") (pin "1") (pinfunction "1_1") (pintype "passive"))
    )
    (net (code "64") (name "Net-(LED17-PadA)") (class "Default")
      (node (ref "LED17") (pin "A") (pinfunction "A_A") (pintype "passive"))
      (node (ref "R39") (pin "1") (pinfunction "1_1") (pintype "passive"))
    )
    (net (code "65") (name "Net-(LED18-PadA)") (class "Default")
      (node (ref "LED18") (pin "A") (pinfunction "A_A") (pintype "passive"))
      (node (ref "R40") (pin "1") (pinfunction "1_1") (pintype "passive"))
    )
    (net (code "66") (name "Net-(LED19-PadA)") (class "Default")
      (node (ref "LED19") (pin "A") (pinfunction "A_A") (pintype "passive"))
      (node (ref "R59") (pin "1") (pinfunction "1_1") (pintype "passive"))
    )
    (net (code "67") (name "Net-(LED20-PadA)") (class "Default")
      (node (ref "LED20") (pin "A") (pinfunction "A_A") (pintype "passive"))
      (node (ref "R60") (pin "1") (pinfunction "1_1") (pintype "passive"))
    )
    (net (code "68") (name "Net-(OK1-A)") (class "Default")
      (node (ref "OK1") (pin "1") (pinfunction "A_1") (pintype "passive"))
      (node (ref "R6") (pin "2") (pinfunction "2_2") (pintype "passive"))
    )
    (net (code "69") (name "Net-(OK1-C)") (class "Default")
      (node (ref "OK1") (pin "2") (pinfunction "C_2") (pintype "passive"))
      (node (ref "X1") (pin "2") (pinfunction "KL_2") (pintype "passive"))
    )
    (net (code "70") (name "Net-(OK2-A)") (class "Default")
      (node (ref "OK2") (pin "1") (pinfunction "A_1") (pintype "passive"))
      (node (ref "R5") (pin "2") (pinfunction "2_2") (pintype "passive"))
    )
    (net (code "71") (name "Net-(OK2-C)") (class "Default")
      (node (ref "OK2") (pin "2") (pinfunction "C_2") (pintype "passive"))
      (node (ref "X1") (pin "4") (pinfunction "KL_4") (pintype "passive"))
    )
    (net (code "72") (name "Net-(OK3-A)") (class "Default")
      (node (ref "OK3") (pin "1") (pinfunction "A_1") (pintype "passive"))
      (node (ref "R8") (pin "2") (pinfunction "2_2") (pintype "passive"))
    )
    (net (code "73") (name "Net-(OK3-C)") (class "Default")
      (node (ref "OK3") (pin "2") (pinfunction "C_2") (pintype "passive"))
      (node (ref "X1") (pin "6") (pinfunction "KL_6") (pintype "passive"))
    )
    (net (code "74") (name "Net-(OK4-A)") (class "Default")
      (node (ref "OK4") (pin "1") (pinfunction "A_1") (pintype "passive"))
      (node (ref "R9") (pin "2") (pinfunction "2_2") (pintype "passive"))
    )
    (net (code "75") (name "Net-(OK4-C)") (class "Default")
      (node (ref "OK4") (pin "2") (pinfunction "C_2") (pintype "passive"))
      (node (ref "X1") (pin "8") (pinfunction "KL_8") (pintype "passive"))
    )
    (net (code "76") (name "Net-(OK5-A)") (class "Default")
      (node (ref "OK5") (pin "1") (pinfunction "A_1") (pintype "passive"))
      (node (ref "R10") (pin "2") (pinfunction "2_2") (pintype "passive"))
    )
    (net (code "77") (name "Net-(OK5-C)") (class "Default")
      (node (ref "OK5") (pin "2") (pinfunction "C_2") (pintype "passive"))
      (node (ref "X2") (pin "2") (pinfunction "KL_2") (pintype "passive"))
    )
    (net (code "78") (name "Net-(OK6-A)") (class "Default")
      (node (ref "OK6") (pin "1") (pinfunction "A_1") (pintype "passive"))
      (node (ref "R11") (pin "2") (pinfunction "2_2") (pintype "passive"))
    )
    (net (code "79") (name "Net-(OK6-C)") (class "Default")
      (node (ref "OK6") (pin "2") (pinfunction "C_2") (pintype "passive"))
      (node (ref "X2") (pin "4") (pinfunction "KL_4") (pintype "passive"))
    )
    (net (code "80") (name "Net-(OK7-A)") (class "Default")
      (node (ref "OK7") (pin "1") (pinfunction "A_1") (pintype "passive"))
      (node (ref "R12") (pin "2") (pinfunction "2_2") (pintype "passive"))
    )
    (net (code "81") (name "Net-(OK7-C)") (class "Default")
      (node (ref "OK7") (pin "2") (pinfunction "C_2") (pintype "passive"))
      (node (ref "X2") (pin "6") (pinfunction "KL_6") (pintype "passive"))
    )
    (net (code "82") (name "Net-(OK8-A)") (class "Default")
      (node (ref "OK8") (pin "1") (pinfunction "A_1") (pintype "passive"))
      (node (ref "R13") (pin "2") (pinfunction "2_2") (pintype "passive"))
    )
    (net (code "83") (name "Net-(OK8-C)") (class "Default")
      (node (ref "OK8") (pin "2") (pinfunction "C_2") (pintype "passive"))
      (node (ref "X2") (pin "8") (pinfunction "KL_8") (pintype "passive"))
    )
    (net (code "84") (name "Net-(T1-B)") (class "Default")
      (node (ref "R42") (pin "1") (pinfunction "1_1") (pintype "passive"))
      (node (ref "T1") (pin "3") (pinfunction "B_3") (pintype "passive"))
    )
    (net (code "85") (name "Net-(T1-E)") (class "Default")
      (node (ref "LED16") (pin "C") (pinfunction "C_C") (pintype "passive"))
      (node (ref "T1") (pin "2") (pinfunction "E_2") (pintype "passive"))
    )
    (net (code "86") (name "Net-(T2-B)") (class "Default")
      (node (ref "R28") (pin "1") (pinfunction "1_1") (pintype "passive"))
      (node (ref "T2") (pin "3") (pinfunction "B_3") (pintype "passive"))
    )
    (net (code "87") (name "Net-(T2-E)") (class "Default")
      (node (ref "D3") (pin "A") (pinfunction "A_A") (pintype "passive"))
      (node (ref "K3") (pin "2") (pinfunction "2_2") (pintype "passive"))
      (node (ref "LED11") (pin "C") (pinfunction "C_C") (pintype "passive"))
      (node (ref "T2") (pin "2") (pinfunction "E_2") (pintype "passive"))
    )
    (net (code "88") (name "Net-(T3-B)") (class "Default")
      (node (ref "R43") (pin "1") (pinfunction "1_1") (pintype "passive"))
      (node (ref "T3") (pin "3") (pinfunction "B_3") (pintype "passive"))
    )
    (net (code "89") (name "Net-(T3-E)") (class "Default")
      (node (ref "LED17") (pin "C") (pinfunction "C_C") (pintype "passive"))
      (node (ref "T3") (pin "2") (pinfunction "E_2") (pintype "passive"))
    )
    (net (code "90") (name "Net-(T4-B)") (class "Default")
      (node (ref "R44") (pin "1") (pinfunction "1_1") (pintype "passive"))
      (node (ref "T4") (pin "3") (pinfunction "B_3") (pintype "passive"))
    )
    (net (code "91") (name "Net-(T4-E)") (class "Default")
      (node (ref "LED18") (pin "C") (pinfunction "C_C") (pintype "passive"))
      (node (ref "T4") (pin "2") (pinfunction "E_2") (pintype "passive"))
    )
    (net (code "92") (name "Net-(T5-B)") (class "Default")
      (node (ref "R33") (pin "1") (pinfunction "1_1") (pintype "passive"))
      (node (ref "R34") (pin "2") (pinfunction "2_2") (pintype "passive"))
      (node (ref "T5") (pin "3") (pinfunction "B_3") (pintype "passive"))
    )
    (net (code "93") (name "Net-(T5-C)") (class "Default")
      (node (ref "LED13") (pin "C") (pinfunction "C_C") (pintype "passive"))
      (node (ref "SG1") (pin "-") (pinfunction "-_-") (pintype "passive"))
      (node (ref "T5") (pin "1") (pinfunction "C_1") (pintype "passive"))
    )
    (net (code "94") (name "Net-(T6-B)") (class "Default")
      (node (ref "R31") (pin "1") (pinfunction "1_1") (pintype "passive"))
      (node (ref "T6") (pin "3") (pinfunction "B_3") (pintype "passive"))
    )
    (net (code "95") (name "Net-(T6-E)") (class "Default")
      (node (ref "D4") (pin "A") (pinfunction "A_A") (pintype "passive"))
      (node (ref "K4") (pin "2") (pinfunction "2_2") (pintype "passive"))
      (node (ref "LED12") (pin "C") (pinfunction "C_C") (pintype "passive"))
      (node (ref "T6") (pin "2") (pinfunction "E_2") (pintype "passive"))
    )
    (net (code "96") (name "Net-(T7-B)") (class "Default")
      (node (ref "R25") (pin "1") (pinfunction "1_1") (pintype "passive"))
      (node (ref "T7") (pin "3") (pinfunction "B_3") (pintype "passive"))
    )
    (net (code "97") (name "Net-(T7-E)") (class "Default")
      (node (ref "D2") (pin "A") (pinfunction "A_A") (pintype "passive"))
      (node (ref "K2") (pin "2") (pinfunction "2_2") (pintype "passive"))
      (node (ref "LED10") (pin "C") (pinfunction "C_C") (pintype "passive"))
      (node (ref "T7") (pin "2") (pinfunction "E_2") (pintype "passive"))
    )
    (net (code "98") (name "Net-(T8-B)") (class "Default")
      (node (ref "R22") (pin "1") (pinfunction "1_1") (pintype "passive"))
      (node (ref "T8") (pin "3") (pinfunction "B_3") (pintype "passive"))
    )
    (net (code "99") (name "Net-(T8-E)") (class "Default")
      (node (ref "D1") (pin "A") (pinfunction "A_A") (pintype "passive"))
      (node (ref "K1") (pin "2") (pinfunction "2_2") (pintype "passive"))
      (node (ref "LED1") (pin "C") (pinfunction "C_C") (pintype "passive"))
      (node (ref "T8") (pin "2") (pinfunction "E_2") (pintype "passive"))
    )
    (net (code "100") (name "Net-(T10-B)") (class "Default")
      (node (ref "R41") (pin "1") (pinfunction "1_1") (pintype "passive"))
      (node (ref "T10") (pin "3") (pinfunction "B_3") (pintype "passive"))
    )
    (net (code "101") (name "Net-(T10-E)") (class "Default")
      (node (ref "LED15") (pin "C") (pinfunction "C_C") (pintype "passive"))
      (node (ref "T10") (pin "2") (pinfunction "E_2") (pintype "passive"))
    )
    (net (code "102") (name "Net-(X1A-KL)") (class "Default")
      (node (ref "R6") (pin "1") (pinfunction "1_1") (pintype "passive"))
      (node (ref "X1") (pin "1") (pinfunction "KL_1") (pintype "passive"))
    )
    (net (code "103") (name "Net-(X1C-KL)") (class "Default")
      (node (ref "R5") (pin "1") (pinfunction "1_1") (pintype "passive"))
      (node (ref "X1") (pin "3") (pinfunction "KL_3") (pintype "passive"))
    )
    (net (code "104") (name "Net-(X1E-KL)") (class "Default")
      (node (ref "R8") (pin "1") (pinfunction "1_1") (pintype "passive"))
      (node (ref "X1") (pin "5") (pinfunction "KL_5") (pintype "passive"))
    )
    (net (code "105") (name "Net-(X1G-KL)") (class "Default")
      (node (ref "R9") (pin "1") (pinfunction "1_1") (pintype "passive"))
      (node (ref "X1") (pin "7") (pinfunction "KL_7") (pintype "passive"))
    )
    (net (code "106") (name "Net-(X2A-KL)") (class "Default")
      (node (ref "R10") (pin "1") (pinfunction "1_1") (pintype "passive"))
      (node (ref "X2") (pin "1") (pinfunction "KL_1") (pintype "passive"))
    )
    (net (code "107") (name "Net-(X2C-KL)") (class "Default")
      (node (ref "R11") (pin "1") (pinfunction "1_1") (pintype "passive"))
      (node (ref "X2") (pin "3") (pinfunction "KL_3") (pintype "passive"))
    )
    (net (code "108") (name "Net-(X2E-KL)") (class "Default")
      (node (ref "R12") (pin "1") (pinfunction "1_1") (pintype "passive"))
      (node (ref "X2") (pin "5") (pinfunction "KL_5") (pintype "passive"))
    )
    (net (code "109") (name "Net-(X2G-KL)") (class "Default")
      (node (ref "R13") (pin "1") (pinfunction "1_1") (pintype "passive"))
      (node (ref "X2") (pin "7") (pinfunction "KL_7") (pintype "passive"))
    )
    (net (code "110") (name "Net-(X3A-KL)") (class "Default")
      (node (ref "K1") (pin "C@1") (pinfunction "P_C@1") (pintype "passive"))
      (node (ref "X3") (pin "1") (pinfunction "KL_1") (pintype "passive"))
    )
    (net (code "111") (name "Net-(X4A-KL)") (class "Default")
      (node (ref "K2") (pin "C@1") (pinfunction "P_C@1") (pintype "passive"))
      (node (ref "X4") (pin "1") (pinfunction "KL_1") (pintype "passive"))
    )
    (net (code "112") (name "Net-(X5A-KL)") (class "Default")
      (node (ref "K3") (pin "C@1") (pinfunction "P_C@1") (pintype "passive"))
      (node (ref "X5") (pin "1") (pinfunction "KL_1") (pintype "passive"))
    )
    (net (code "113") (name "Net-(X6A-KL)") (class "Default")
      (node (ref "K4") (pin "C@1") (pinfunction "P_C@1") (pintype "passive"))
      (node (ref "X6") (pin "1") (pinfunction "KL_1") (pintype "passive"))
    )
    (net (code "114") (name "unconnected-(J2-Pad2)") (class "Default")
      (node (ref "J2") (pin "2") (pinfunction "2_2") (pintype "passive"))
    )
    (net (code "115") (name "unconnected-(K1B-P-PadC@2)") (class "Default")
      (node (ref "K1") (pin "C@2") (pinfunction "P_C@2") (pintype "passive"))
    )
    (net (code "116") (name "unconnected-(K2B-P-PadC@2)") (class "Default")
      (node (ref "K2") (pin "C@2") (pinfunction "P_C@2") (pintype "passive"))
    )
    (net (code "117") (name "unconnected-(K3B-P-PadC@2)") (class "Default")
      (node (ref "K3") (pin "C@2") (pinfunction "P_C@2") (pintype "passive"))
    )
    (net (code "118") (name "unconnected-(K4B-P-PadC@2)") (class "Default")
      (node (ref "K4") (pin "C@2") (pinfunction "P_C@2") (pintype "passive"))
    )
    (net (code "119") (name "unconnected-(S1-1.2-Pad2)") (class "Default")
      (node (ref "S1") (pin "2") (pinfunction "1.2_2") (pintype "passive"))
    )
    (net (code "120") (name "unconnected-(S1-2.2-Pad4)") (class "Default")
      (node (ref "S1") (pin "4") (pinfunction "2.2_4") (pintype "passive"))
    )
    (net (code "121") (name "unconnected-(S1-SH-Pad5)") (class "Default")
      (node (ref "S1") (pin "5") (pinfunction "SH_5") (pintype "passive"))
    )
    (net (code "122") (name "unconnected-(SV6-Pad1)") (class "Default")
      (node (ref "SV6") (pin "1") (pinfunction "1_1") (pintype "passive"))
    )
    (net (code "123") (name "unconnected-(SV6-Pad10)") (class "Default")
      (node (ref "SV6") (pin "10") (pinfunction "10_10") (pintype "passive"))
    )
    (net (code "124") (name "unconnected-(U$2-Pad0)") (class "Default")
      (node (ref "U$2") (pin "0") (pinfunction "0_0") (pintype "bidirectional"))
    )
    (net (code "125") (name "unconnected-(U$2-Pad4)") (class "Default")
      (node (ref "U$2") (pin "4") (pinfunction "4_4") (pintype "bidirectional"))
    )
    (net (code "126") (name "unconnected-(U$2-Pad13)") (class "Default")
      (node (ref "U$2") (pin "13") (pinfunction "13_13") (pintype "bidirectional"))
    )
    (net (code "127") (name "unconnected-(U$2-PadRST)") (class "Default")
      (node (ref "U$2") (pin "RST") (pinfunction "RST_RST") (pintype "bidirectional"))
    )
    (net (code "128") (name "unconnected-(U$2-PadRXD)") (class "Default")
      (node (ref "U$2") (pin "RXD") (pinfunction "RXD_RXD") (pintype "bidirectional"))
    )
    (net (code "129") (name "unconnected-(U$2-PadTXD)") (class "Default")
      (node (ref "U$2") (pin "TXD") (pinfunction "TXD_TXD") (pintype "bidirectional"))
    )
  )
)
